# OpenEVSE_ESP32_v1.net
KiCad netlist of a schematic drawn in EAGLE
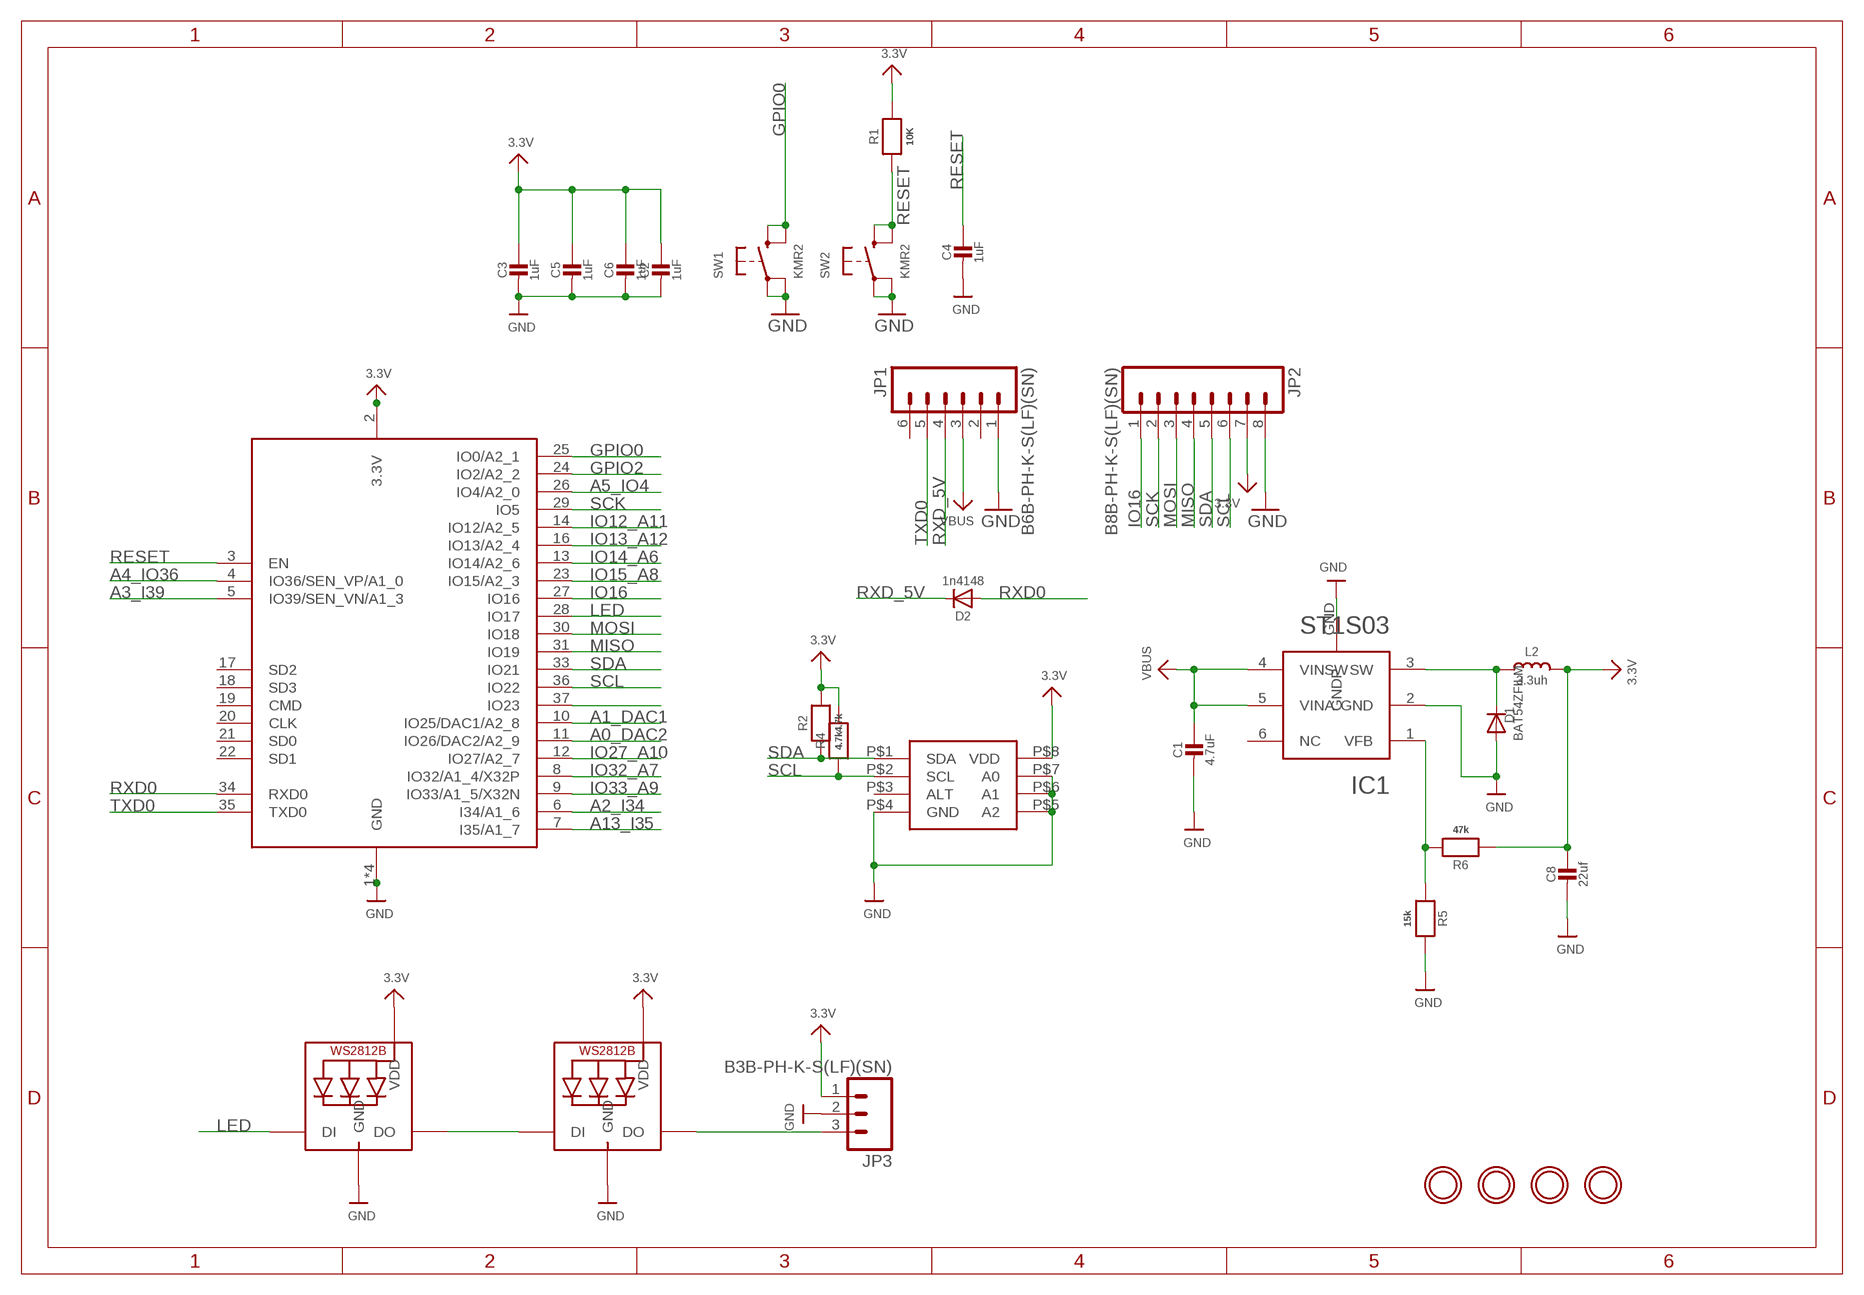
[diagram p0: schematic, sheet 1]

(export (version "E")
  (design (tool "Eeschema 10.0.6"))
  (components
    (comp (ref "C1")
      (value "4.7uF")
      (footprint "eagle-import:0603-NO")
      (libsource (lib "eagle-import") (part "CAP_CERAMIC0603_NO"))
    )
    (comp (ref "C2")
      (value "1uF")
      (footprint "eagle-import:0603-NO")
      (libsource (lib "eagle-import") (part "CAP_CERAMIC0603_NO"))
    )
    (comp (ref "C3")
      (value "1uF")
      (footprint "eagle-import:0603-NO")
      (libsource (lib "eagle-import") (part "CAP_CERAMIC0603_NO"))
    )
    (comp (ref "C4")
      (value "1uF")
      (footprint "eagle-import:0603-NO")
      (libsource (lib "eagle-import") (part "CAP_CERAMIC0603_NO"))
    )
    (comp (ref "C5")
      (value "1uF")
      (footprint "eagle-import:0603-NO")
      (libsource (lib "eagle-import") (part "CAP_CERAMIC0603_NO"))
    )
    (comp (ref "C6")
      (value "1uF")
      (footprint "eagle-import:0603-NO")
      (libsource (lib "eagle-import") (part "CAP_CERAMIC0603_NO"))
    )
    (comp (ref "C8")
      (value "22uf")
      (footprint "eagle-import:0603-NO")
      (libsource (lib "eagle-import") (part "CAP_CERAMIC0603_NO"))
    )
    (comp (ref "D1")
      (value "BAT54ZFILM")
      (footprint "eagle-import:SOD-123")
      (libsource (lib "eagle-import") (part "DIODESOD-123"))
    )
    (comp (ref "D2")
      (value "1n4148")
      (footprint "eagle-import:SOD-323")
      (libsource (lib "eagle-import") (part "DIODESOD-323"))
    )
    (comp (ref "IC1")
      (value "ST1S03")
      (footprint "eagle-import:DFQN6D")
      (libsource (lib "eagle-import") (part "ST1S03"))
    )
    (comp (ref "IC2")
      (value "MCP9808")
      (footprint "eagle-import:MSOP8")
      (libsource (lib "eagle-import") (part "MCP9808"))
    )
    (comp (ref "JP1")
      (value "B6B-PH-K-S(LF)(SN)")
      (footprint "eagle-import:JST6")
      (libsource (lib "eagle-import") (part "JST6"))
    )
    (comp (ref "JP2")
      (value "B8B-PH-K-S(LF)(SN)")
      (footprint "eagle-import:JST8")
      (libsource (lib "eagle-import") (part "JST8"))
    )
    (comp (ref "JP3")
      (value "B3B-PH-K-S(LF)(SN)")
      (footprint "eagle-import:JST-3-PTH-VERT")
      (libsource (lib "eagle-import") (part "M03JST-PTH-VERT"))
    )
    (comp (ref "L2")
      (value "3.3uh")
      (footprint "eagle-import:MICROBUILDER_INDUCTOR_5X5MM_NR5040_NOTHERMALS")
      (libsource (lib "eagle-import") (part "MICROBUILDER_INDUCTORNR5040"))
    )
    (comp (ref "LED1")
      (value "SK6812MINI")
      (footprint "eagle-import:MICROBUILDER_LED3535")
      (libsource (lib "eagle-import") (part "MICROBUILDER_WS2812B3535"))
    )
    (comp (ref "LED2")
      (value "SK6812MINI")
      (footprint "eagle-import:MICROBUILDER_LED3535")
      (libsource (lib "eagle-import") (part "MICROBUILDER_WS2812B3535"))
    )
    (comp (ref "R1")
      (value "10K")
      (footprint "eagle-import:0603-NO")
      (libsource (lib "eagle-import") (part "RESISTOR_0603_NOOUT"))
    )
    (comp (ref "R2")
      (value "4.7k")
      (footprint "eagle-import:0603-NO")
      (libsource (lib "eagle-import") (part "RESISTOR_0603_NOOUT"))
    )
    (comp (ref "R4")
      (value "4.7k")
      (footprint "eagle-import:0603-NO")
      (libsource (lib "eagle-import") (part "RESISTOR_0603_NOOUT"))
    )
    (comp (ref "R5")
      (value "15k")
      (footprint "eagle-import:0603-NO")
      (libsource (lib "eagle-import") (part "RESISTOR_0603_NOOUT"))
    )
    (comp (ref "R6")
      (value "47k")
      (footprint "eagle-import:0603-NO")
      (libsource (lib "eagle-import") (part "RESISTOR_0603_NOOUT"))
    )
    (comp (ref "SW1")
      (value "KMR2")
      (footprint "eagle-import:BTN_KMR2_4.6X2.8")
      (libsource (lib "eagle-import") (part "SWITCH_TACT_SMT4.6X2.8"))
    )
    (comp (ref "SW2")
      (value "KMR2")
      (footprint "eagle-import:BTN_KMR2_4.6X2.8")
      (libsource (lib "eagle-import") (part "SWITCH_TACT_SMT4.6X2.8"))
    )
    (comp (ref "U$8")
      (value "MOUNTINGHOLE2.5")
      (footprint "eagle-import:MOUNTINGHOLE_2.5_PLATED")
      (libsource (lib "eagle-import") (part "MOUNTINGHOLE2.5"))
    )
    (comp (ref "U$17")
      (value "MOUNTINGHOLE2.5")
      (footprint "eagle-import:MOUNTINGHOLE_2.5_PLATED")
      (libsource (lib "eagle-import") (part "MOUNTINGHOLE2.5"))
    )
    (comp (ref "U$25")
      (value "MOUNTINGHOLE2.5")
      (footprint "eagle-import:MOUNTINGHOLE_2.5_PLATED")
      (libsource (lib "eagle-import") (part "MOUNTINGHOLE2.5"))
    )
    (comp (ref "U$27")
      (value "MOUNTINGHOLE2.5")
      (footprint "eagle-import:MOUNTINGHOLE_2.5_PLATED")
      (libsource (lib "eagle-import") (part "MOUNTINGHOLE2.5"))
    )
    (comp (ref "X2")
      (value "ESP32-WROOM-32")
      (footprint "eagle-import:WROOM32_SKINNY")
      (libsource (lib "eagle-import") (part "ESP32_WROOM32_SKINNY"))
    )
  )
  (nets
    (net (code "1") (name "/A0_DAC2") (class "Default")
      (node (ref "X2") (pin "11") (pinfunction "IO26/DAC2/A2_9_11") (pintype "bidirectional"))
    )
    (net (code "2") (name "/A1_DAC1") (class "Default")
      (node (ref "X2") (pin "10") (pinfunction "IO25/DAC1/A2_8_10") (pintype "bidirectional"))
    )
    (net (code "3") (name "/A2_I34") (class "Default")
      (node (ref "X2") (pin "6") (pinfunction "I34/A1_6_6") (pintype "bidirectional"))
    )
    (net (code "4") (name "/A3_I39") (class "Default")
      (node (ref "X2") (pin "5") (pinfunction "IO39/SEN_VN/A1_3_5") (pintype "passive"))
    )
    (net (code "5") (name "/A4_IO36") (class "Default")
      (node (ref "X2") (pin "4") (pinfunction "IO36/SEN_VP/A1_0_4") (pintype "passive"))
    )
    (net (code "6") (name "/A5_IO4") (class "Default")
      (node (ref "X2") (pin "26") (pinfunction "IO4/A2_0_26") (pintype "bidirectional"))
    )
    (net (code "7") (name "/A13_I35") (class "Default")
      (node (ref "X2") (pin "7") (pinfunction "I35/A1_7_7") (pintype "bidirectional"))
    )
    (net (code "8") (name "/GPIO0") (class "Default")
      (node (ref "SW1") (pin "B") (pinfunction "S_B") (pintype "passive"))
      (node (ref "SW1") (pin "B'") (pinfunction "S1_B'") (pintype "passive"))
      (node (ref "X2") (pin "25") (pinfunction "IO0/A2_1_25") (pintype "bidirectional"))
    )
    (net (code "9") (name "/GPIO2") (class "Default")
      (node (ref "X2") (pin "24") (pinfunction "IO2/A2_2_24") (pintype "bidirectional"))
    )
    (net (code "10") (name "/IO12_A11") (class "Default")
      (node (ref "X2") (pin "14") (pinfunction "IO12/A2_5_14") (pintype "bidirectional"))
    )
    (net (code "11") (name "/IO13_A12") (class "Default")
      (node (ref "X2") (pin "16") (pinfunction "IO13/A2_4_16") (pintype "bidirectional"))
    )
    (net (code "12") (name "/IO14_A6") (class "Default")
      (node (ref "X2") (pin "13") (pinfunction "IO14/A2_6_13") (pintype "bidirectional"))
    )
    (net (code "13") (name "/IO15_A8") (class "Default")
      (node (ref "X2") (pin "23") (pinfunction "IO15/A2_3_23") (pintype "bidirectional"))
    )
    (net (code "14") (name "/IO16") (class "Default")
      (node (ref "JP2") (pin "1") (pinfunction "1_1") (pintype "passive"))
      (node (ref "X2") (pin "27") (pinfunction "IO16_27") (pintype "bidirectional"))
    )
    (net (code "15") (name "/IO27_A10") (class "Default")
      (node (ref "X2") (pin "12") (pinfunction "IO27/A2_7_12") (pintype "bidirectional"))
    )
    (net (code "16") (name "/IO32_A7") (class "Default")
      (node (ref "X2") (pin "8") (pinfunction "IO32/A1_4/X32P_8") (pintype "bidirectional"))
    )
    (net (code "17") (name "/IO33_A9") (class "Default")
      (node (ref "X2") (pin "9") (pinfunction "IO33/A1_5/X32N_9") (pintype "bidirectional"))
    )
    (net (code "18") (name "/LED") (class "Default")
      (node (ref "LED1") (pin "1") (pinfunction "DI_1") (pintype "input"))
      (node (ref "X2") (pin "28") (pinfunction "IO17_28") (pintype "bidirectional"))
    )
    (net (code "19") (name "/MISO") (class "Default")
      (node (ref "JP2") (pin "4") (pinfunction "4_4") (pintype "passive"))
      (node (ref "X2") (pin "31") (pinfunction "IO19_31") (pintype "bidirectional"))
    )
    (net (code "20") (name "/MOSI") (class "Default")
      (node (ref "JP2") (pin "3") (pinfunction "3_3") (pintype "passive"))
      (node (ref "X2") (pin "30") (pinfunction "IO18_30") (pintype "bidirectional"))
    )
    (net (code "21") (name "/RESET") (class "Default")
      (node (ref "C4") (pin "1") (pinfunction "1_1") (pintype "passive"))
      (node (ref "R1") (pin "1") (pinfunction "1_1") (pintype "passive"))
      (node (ref "SW2") (pin "B") (pinfunction "S_B") (pintype "passive"))
      (node (ref "SW2") (pin "B'") (pinfunction "S1_B'") (pintype "passive"))
      (node (ref "X2") (pin "3") (pinfunction "EN_3") (pintype "input"))
    )
    (net (code "22") (name "/RXD0") (class "Default")
      (node (ref "D2") (pin "A") (pinfunction "A_A") (pintype "passive"))
      (node (ref "X2") (pin "34") (pinfunction "RXD0_34") (pintype "input"))
    )
    (net (code "23") (name "/RXD_5V") (class "Default")
      (node (ref "D2") (pin "C") (pinfunction "C_C") (pintype "passive"))
      (node (ref "JP1") (pin "4") (pinfunction "4_4") (pintype "passive"))
    )
    (net (code "24") (name "/SCK") (class "Default")
      (node (ref "JP2") (pin "2") (pinfunction "2_2") (pintype "passive"))
      (node (ref "X2") (pin "29") (pinfunction "IO5_29") (pintype "bidirectional"))
    )
    (net (code "25") (name "/SCL") (class "Default")
      (node (ref "IC2") (pin "P$2") (pinfunction "SCL_P$2") (pintype "bidirectional"))
      (node (ref "JP2") (pin "6") (pinfunction "6_6") (pintype "passive"))
      (node (ref "R4") (pin "1") (pinfunction "1_1") (pintype "passive"))
      (node (ref "X2") (pin "36") (pinfunction "IO22_36") (pintype "bidirectional"))
    )
    (net (code "26") (name "/SDA") (class "Default")
      (node (ref "IC2") (pin "P$1") (pinfunction "SDA_P$1") (pintype "bidirectional"))
      (node (ref "JP2") (pin "5") (pinfunction "5_5") (pintype "passive"))
      (node (ref "R2") (pin "1") (pinfunction "1_1") (pintype "passive"))
      (node (ref "X2") (pin "33") (pinfunction "IO21_33") (pintype "bidirectional"))
    )
    (net (code "27") (name "/TXD0") (class "Default")
      (node (ref "JP1") (pin "5") (pinfunction "5_5") (pintype "passive"))
      (node (ref "X2") (pin "35") (pinfunction "TXD0_35") (pintype "output"))
    )
    (net (code "28") (name "3.3V") (class "Default")
      (node (ref "C2") (pin "1") (pinfunction "1_1") (pintype "passive"))
      (node (ref "C3") (pin "1") (pinfunction "1_1") (pintype "passive"))
      (node (ref "C5") (pin "1") (pinfunction "1_1") (pintype "passive"))
      (node (ref "C6") (pin "1") (pinfunction "1_1") (pintype "passive"))
      (node (ref "C8") (pin "1") (pinfunction "1_1") (pintype "passive"))
      (node (ref "IC2") (pin "P$8") (pinfunction "VDD_P$8") (pintype "bidirectional"))
      (node (ref "JP2") (pin "7") (pinfunction "7_7") (pintype "passive"))
      (node (ref "JP3") (pin "1") (pinfunction "1_1") (pintype "passive"))
      (node (ref "L2") (pin "P$2") (pinfunction "2_P$2") (pintype "passive"))
      (node (ref "LED1") (pin "2") (pinfunction "VDD_2") (pintype "power_in"))
      (node (ref "LED2") (pin "2") (pinfunction "VDD_2") (pintype "power_in"))
      (node (ref "R1") (pin "2") (pinfunction "2_2") (pintype "passive"))
      (node (ref "R2") (pin "2") (pinfunction "2_2") (pintype "passive"))
      (node (ref "R4") (pin "2") (pinfunction "2_2") (pintype "passive"))
      (node (ref "R6") (pin "1") (pinfunction "1_1") (pintype "passive"))
      (node (ref "X2") (pin "2") (pinfunction "3.3V_2") (pintype "passive"))
    )
    (net (code "29") (name "GND") (class "Default")
      (node (ref "C1") (pin "2") (pinfunction "2_2") (pintype "passive"))
      (node (ref "C2") (pin "2") (pinfunction "2_2") (pintype "passive"))
      (node (ref "C3") (pin "2") (pinfunction "2_2") (pintype "passive"))
      (node (ref "C4") (pin "2") (pinfunction "2_2") (pintype "passive"))
      (node (ref "C5") (pin "2") (pinfunction "2_2") (pintype "passive"))
      (node (ref "C6") (pin "2") (pinfunction "2_2") (pintype "passive"))
      (node (ref "C8") (pin "2") (pinfunction "2_2") (pintype "passive"))
      (node (ref "D1") (pin "A") (pinfunction "A_A") (pintype "passive"))
      (node (ref "IC1") (pin "2") (pinfunction "GND_2") (pintype "bidirectional"))
      (node (ref "IC1") (pin "GND") (pinfunction "GNDP_GND") (pintype "bidirectional"))
      (node (ref "IC2") (pin "P$4") (pinfunction "GND_P$4") (pintype "bidirectional"))
      (node (ref "IC2") (pin "P$5") (pinfunction "A2_P$5") (pintype "bidirectional"))
      (node (ref "IC2") (pin "P$6") (pinfunction "A1_P$6") (pintype "bidirectional"))
      (node (ref "IC2") (pin "P$7") (pinfunction "A0_P$7") (pintype "bidirectional"))
      (node (ref "JP1") (pin "1") (pinfunction "1_1") (pintype "passive"))
      (node (ref "JP2") (pin "8") (pinfunction "8_8") (pintype "passive"))
      (node (ref "JP3") (pin "2") (pinfunction "2_2") (pintype "passive"))
      (node (ref "LED1") (pin "4") (pinfunction "GND_4") (pintype "power_in"))
      (node (ref "LED2") (pin "4") (pinfunction "GND_4") (pintype "power_in"))
      (node (ref "R5") (pin "2") (pinfunction "2_2") (pintype "passive"))
      (node (ref "SW1") (pin "A") (pinfunction "P_A") (pintype "passive"))
      (node (ref "SW1") (pin "A'") (pinfunction "P1_A'") (pintype "passive"))
      (node (ref "SW2") (pin "A") (pinfunction "P_A") (pintype "passive"))
      (node (ref "SW2") (pin "A'") (pinfunction "P1_A'") (pintype "passive"))
      (node (ref "X2") (pin "1") (pinfunction "GND_1") (pintype "passive"))
      (node (ref "X2") (pin "15") (pinfunction "GND_15") (pintype "passive"))
      (node (ref "X2") (pin "38") (pinfunction "GND_38") (pintype "passive"))
      (node (ref "X2") (pin "P$1") (pinfunction "GND_P$1") (pintype "passive"))
    )
    (net (code "30") (name "Net-(IC1-SW)") (class "Default")
      (node (ref "D1") (pin "C") (pinfunction "C_C") (pintype "passive"))
      (node (ref "IC1") (pin "3") (pinfunction "SW_3") (pintype "bidirectional"))
      (node (ref "L2") (pin "P$1") (pinfunction "1_P$1") (pintype "passive"))
    )
    (net (code "31") (name "Net-(IC1-VFB)") (class "Default")
      (node (ref "IC1") (pin "1") (pinfunction "VFB_1") (pintype "bidirectional"))
      (node (ref "R5") (pin "1") (pinfunction "1_1") (pintype "passive"))
      (node (ref "R6") (pin "2") (pinfunction "2_2") (pintype "passive"))
    )
    (net (code "32") (name "Net-(LED1-DO)") (class "Default")
      (node (ref "LED1") (pin "3") (pinfunction "DO_3") (pintype "output"))
      (node (ref "LED2") (pin "1") (pinfunction "DI_1") (pintype "input"))
    )
    (net (code "33") (name "Net-(LED2-DO)") (class "Default")
      (node (ref "JP3") (pin "3") (pinfunction "3_3") (pintype "passive"))
      (node (ref "LED2") (pin "3") (pinfunction "DO_3") (pintype "output"))
    )
    (net (code "34") (name "VBUS") (class "Default")
      (node (ref "C1") (pin "1") (pinfunction "1_1") (pintype "passive"))
      (node (ref "IC1") (pin "4") (pinfunction "VINSW_4") (pintype "bidirectional"))
      (node (ref "IC1") (pin "5") (pinfunction "VINA_5") (pintype "bidirectional"))
      (node (ref "JP1") (pin "3") (pinfunction "3_3") (pintype "passive"))
    )
    (net (code "35") (name "unconnected-(IC1-NC-Pad6)") (class "Default")
      (node (ref "IC1") (pin "6") (pinfunction "NC_6") (pintype "bidirectional"))
    )
    (net (code "36") (name "unconnected-(IC2-ALT-PadP$3)") (class "Default")
      (node (ref "IC2") (pin "P$3") (pinfunction "ALT_P$3") (pintype "bidirectional"))
    )
    (net (code "37") (name "unconnected-(JP1-Pad2)") (class "Default")
      (node (ref "JP1") (pin "2") (pinfunction "2_2") (pintype "passive"))
    )
    (net (code "38") (name "unconnected-(JP1-Pad6)") (class "Default")
      (node (ref "JP1") (pin "6") (pinfunction "6_6") (pintype "passive"))
    )
    (net (code "39") (name "unconnected-(X2-CLK-Pad20)") (class "Default")
      (node (ref "X2") (pin "20") (pinfunction "CLK_20") (pintype "bidirectional"))
    )
    (net (code "40") (name "unconnected-(X2-CMD-Pad19)") (class "Default")
      (node (ref "X2") (pin "19") (pinfunction "CMD_19") (pintype "bidirectional"))
    )
    (net (code "41") (name "unconnected-(X2-IO23-Pad37)") (class "Default")
      (node (ref "X2") (pin "37") (pinfunction "IO23_37") (pintype "bidirectional"))
    )
    (net (code "42") (name "unconnected-(X2-SD0-Pad21)") (class "Default")
      (node (ref "X2") (pin "21") (pinfunction "SD0_21") (pintype "bidirectional"))
    )
    (net (code "43") (name "unconnected-(X2-SD1-Pad22)") (class "Default")
      (node (ref "X2") (pin "22") (pinfunction "SD1_22") (pintype "bidirectional"))
    )
    (net (code "44") (name "unconnected-(X2-SD2-Pad17)") (class "Default")
      (node (ref "X2") (pin "17") (pinfunction "SD2_17") (pintype "bidirectional"))
    )
    (net (code "45") (name "unconnected-(X2-SD3-Pad18)") (class "Default")
      (node (ref "X2") (pin "18") (pinfunction "SD3_18") (pintype "bidirectional"))
    )
  )
)
